# facewhisperer.net
KiCad netlist of a schematic drawn in EAGLE
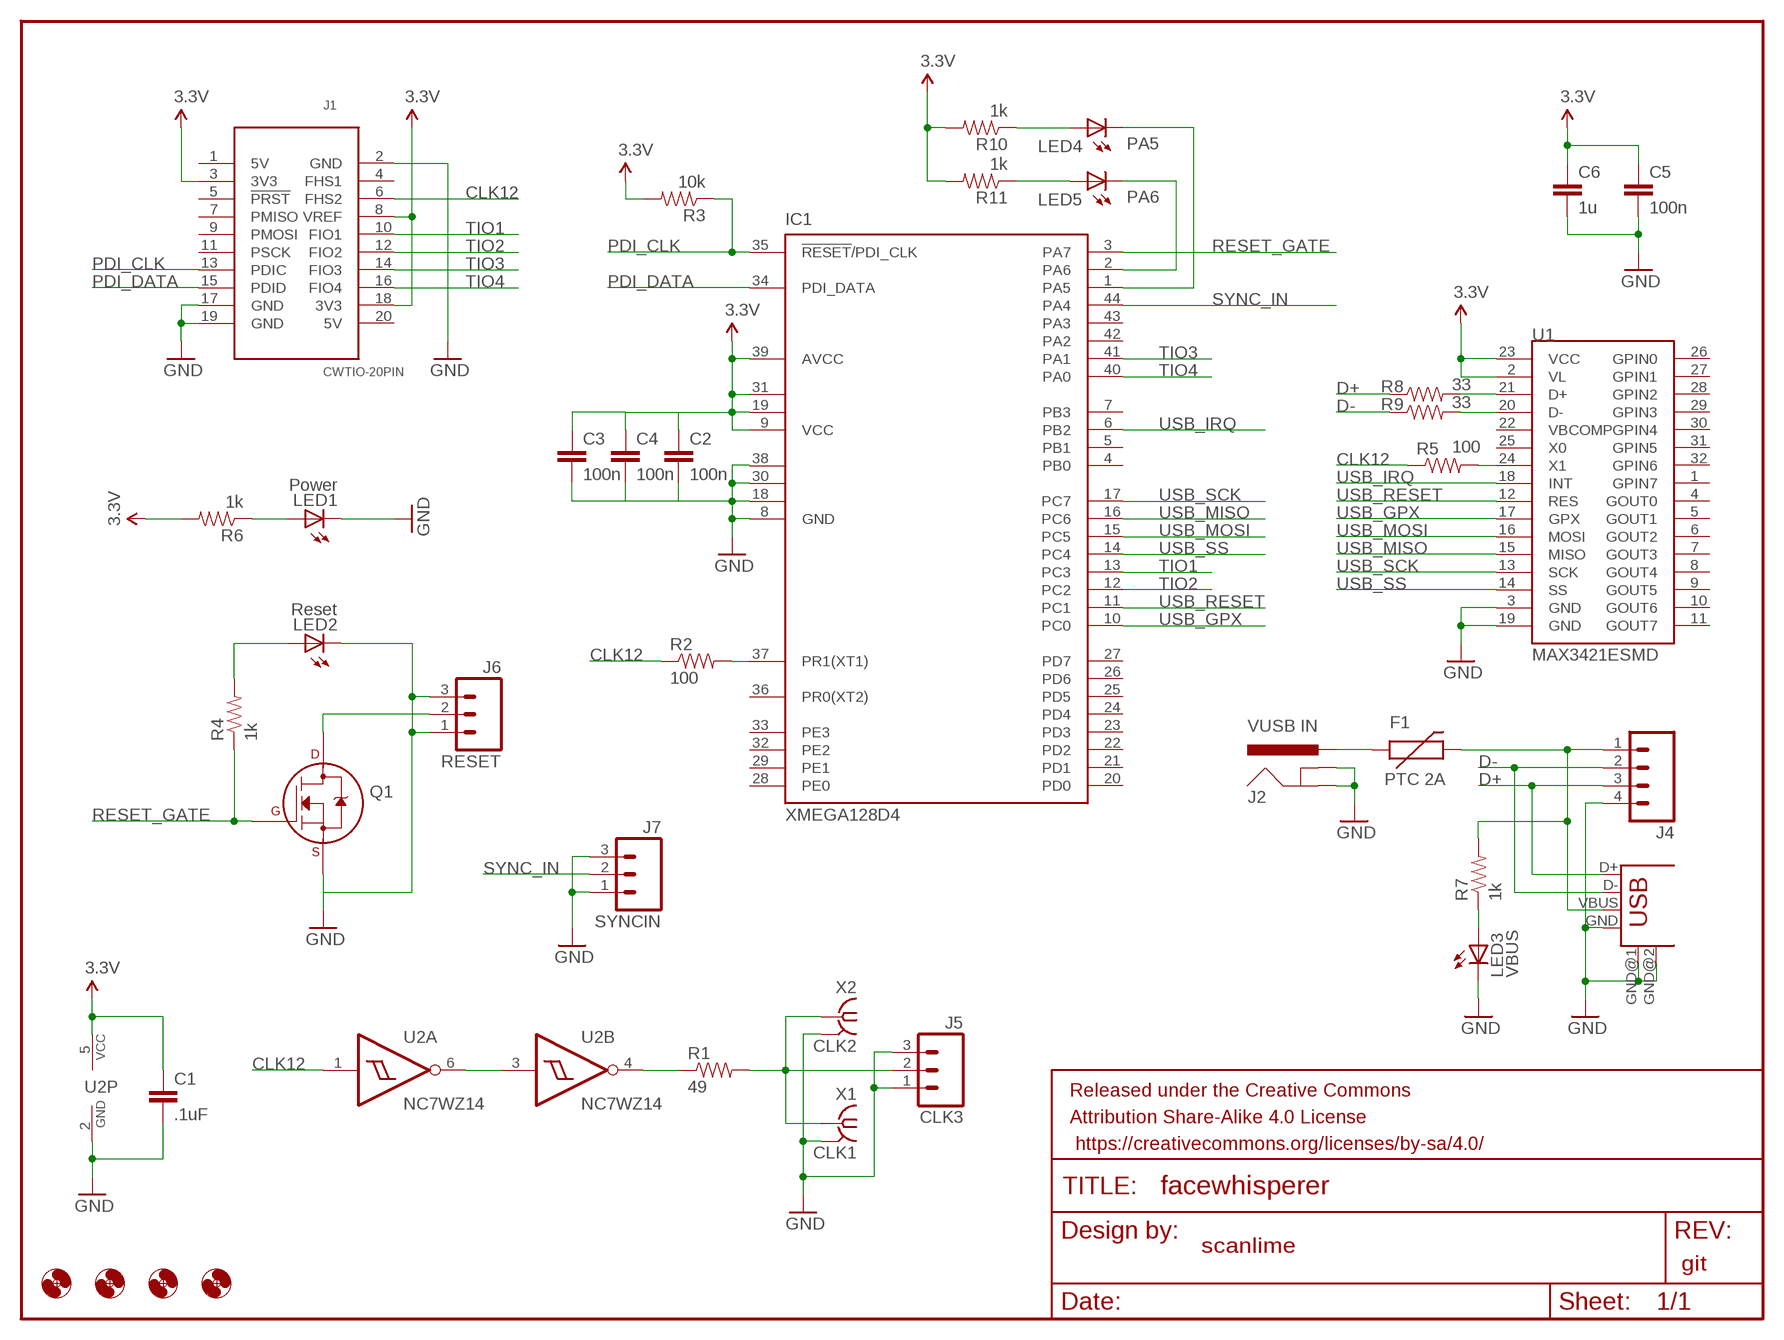
[diagram p0: schematic, sheet 1]

(export (version "E")
  (design (tool "Eeschema 10.0.6"))
  (components
    (comp (ref "C1")
      (value ".1uF")
      (footprint "eagle-import:0805")
      (libsource (lib "eagle-import") (part "CAP0805"))
    )
    (comp (ref "C2")
      (value "100n")
      (footprint "eagle-import:0805")
      (libsource (lib "eagle-import") (part "CAP0805"))
    )
    (comp (ref "C3")
      (value "100n")
      (footprint "eagle-import:0805")
      (libsource (lib "eagle-import") (part "CAP0805"))
    )
    (comp (ref "C4")
      (value "100n")
      (footprint "eagle-import:0805")
      (libsource (lib "eagle-import") (part "CAP0805"))
    )
    (comp (ref "C5")
      (value "100n")
      (footprint "eagle-import:0805")
      (libsource (lib "eagle-import") (part "CAP0805"))
    )
    (comp (ref "C6")
      (value "1u")
      (footprint "eagle-import:0805")
      (libsource (lib "eagle-import") (part "CAP0805"))
    )
    (comp (ref "F1")
      (value "PTC 2A")
      (footprint "eagle-import:PTC-1206-WIDE")
      (libsource (lib "eagle-import") (part "PTCSMD-W"))
    )
    (comp (ref "FRAME1")
      (value "FRAME-LETTERNO_PACKAGE")
      (footprint "eagle-import:DUMMY")
      (fields (field (name "DESIGNER") "Nobody"))
      (libsource (lib "eagle-import") (part "FRAME-LETTERNO_PACKAGE"))
    )
    (comp (ref "H1")
      (value "MOUNT-HOLE3.2")
      (footprint "eagle-import:3,2")
      (libsource (lib "eagle-import") (part "MOUNT-HOLE3.2"))
    )
    (comp (ref "H2")
      (value "MOUNT-HOLE3.2")
      (footprint "eagle-import:3,2")
      (libsource (lib "eagle-import") (part "MOUNT-HOLE3.2"))
    )
    (comp (ref "H3")
      (value "MOUNT-HOLE3.2")
      (footprint "eagle-import:3,2")
      (libsource (lib "eagle-import") (part "MOUNT-HOLE3.2"))
    )
    (comp (ref "H4")
      (value "MOUNT-HOLE3.2")
      (footprint "eagle-import:3,2")
      (libsource (lib "eagle-import") (part "MOUNT-HOLE3.2"))
    )
    (comp (ref "IC1")
      (value "XMEGA128D4")
      (footprint "eagle-import:TQFP44")
      (libsource (lib "eagle-import") (part "XMEGA16A4A"))
    )
    (comp (ref "J1")
      (value "CWTIO-20PIN")
      (footprint "eagle-import:PINSHRD_PTH_2X10")
      (libsource (lib "eagle-import") (part "CWTIO-20PIN"))
    )
    (comp (ref "J2")
      (value "VUSB IN")
      (footprint "eagle-import:POWER_JACK_PTH")
      (libsource (lib "eagle-import") (part "POWER_JACKPTH"))
    )
    (comp (ref "J3")
      (value "USB-A-H")
      (footprint "eagle-import:USB-A-H")
      (libsource (lib "eagle-import") (part "USB-A-H"))
    )
    (comp (ref "J4")
      (value "M04LOCK_LONGPADS")
      (footprint "eagle-import:1X04_LOCK_LONGPADS")
      (libsource (lib "eagle-import") (part "M04LOCK_LONGPADS"))
    )
    (comp (ref "J5")
      (value "CLK3")
      (footprint "eagle-import:1X03_LOCK_LONGPADS")
      (libsource (lib "eagle-import") (part "M03LOCK_LONGPADS"))
    )
    (comp (ref "J6")
      (value "RESET")
      (footprint "eagle-import:1X03_LOCK_LONGPADS")
      (libsource (lib "eagle-import") (part "M03LOCK_LONGPADS"))
    )
    (comp (ref "J7")
      (value "SYNCIN")
      (footprint "eagle-import:1X03_LOCK_LONGPADS")
      (libsource (lib "eagle-import") (part "M03LOCK_LONGPADS"))
    )
    (comp (ref "LED1")
      (value "Power")
      (footprint "eagle-import:1206")
      (libsource (lib "eagle-import") (part "LEDSMT1206"))
    )
    (comp (ref "LED2")
      (value "Reset")
      (footprint "eagle-import:1206")
      (libsource (lib "eagle-import") (part "LEDSMT1206"))
    )
    (comp (ref "LED3")
      (value "VBUS")
      (footprint "eagle-import:1206")
      (libsource (lib "eagle-import") (part "LEDSMT1206"))
    )
    (comp (ref "LED4")
      (value "PA5")
      (footprint "eagle-import:1206")
      (libsource (lib "eagle-import") (part "LEDSMT1206"))
    )
    (comp (ref "LED5")
      (value "PA6")
      (footprint "eagle-import:1206")
      (libsource (lib "eagle-import") (part "LEDSMT1206"))
    )
    (comp (ref "Q1")
      (value "2N7002_SOT23")
      (footprint "eagle-import:SOT-23")
      (libsource (lib "eagle-import") (part "2N700_SOT232"))
    )
    (comp (ref "R1")
      (value "49")
      (footprint "eagle-import:0805")
      (libsource (lib "eagle-import") (part "RESISTOR0805-RES"))
    )
    (comp (ref "R2")
      (value "100")
      (footprint "eagle-import:0805")
      (libsource (lib "eagle-import") (part "RESISTOR0805-RES"))
    )
    (comp (ref "R3")
      (value "10k")
      (footprint "eagle-import:0805")
      (libsource (lib "eagle-import") (part "RESISTOR0805-RES"))
    )
    (comp (ref "R4")
      (value "1k")
      (footprint "eagle-import:0805")
      (libsource (lib "eagle-import") (part "RESISTOR0805-RES"))
    )
    (comp (ref "R5")
      (value "100")
      (footprint "eagle-import:0805")
      (libsource (lib "eagle-import") (part "RESISTOR0805-RES"))
    )
    (comp (ref "R6")
      (value "1k")
      (footprint "eagle-import:0805")
      (libsource (lib "eagle-import") (part "RESISTOR0805-RES"))
    )
    (comp (ref "R7")
      (value "1k")
      (footprint "eagle-import:0805")
      (libsource (lib "eagle-import") (part "RESISTOR0805-RES"))
    )
    (comp (ref "R8")
      (value "33")
      (footprint "eagle-import:0805")
      (libsource (lib "eagle-import") (part "RESISTOR0805-RES"))
    )
    (comp (ref "R9")
      (value "33")
      (footprint "eagle-import:0805")
      (libsource (lib "eagle-import") (part "RESISTOR0805-RES"))
    )
    (comp (ref "R10")
      (value "1k")
      (footprint "eagle-import:0805")
      (libsource (lib "eagle-import") (part "RESISTOR0805-RES"))
    )
    (comp (ref "R11")
      (value "1k")
      (footprint "eagle-import:0805")
      (libsource (lib "eagle-import") (part "RESISTOR0805-RES"))
    )
    (comp (ref "U1")
      (value "MAX3421ESMD")
      (footprint "eagle-import:TQFP32-5MM-MILLABLE")
      (libsource (lib "eagle-import") (part "MAX3421ESMD"))
    )
    (comp (ref "U2")
      (value "NC7WZ14")
      (footprint "eagle-import:SC70-6-MILLABLE")
      (libsource (lib "eagle-import") (part "NC7WZ14"))
    )
    (comp (ref "X1")
      (value "CLK1")
      (footprint "eagle-import:J502-ND-142-0711-821_826-NOSILK")
      (libsource (lib "eagle-import") (part "SMA-NOSILK"))
    )
    (comp (ref "X2")
      (value "CLK2")
      (footprint "eagle-import:J502-ND-142-0711-821_826-NOSILK")
      (libsource (lib "eagle-import") (part "SMA-NOSILK"))
    )
  )
  (nets
    (net (code "1") (name "/CLK12") (class "Default")
      (node (ref "J1") (pin "6") (pinfunction "FHS2_6") (pintype "bidirectional"))
      (node (ref "R2") (pin "1") (pinfunction "1_1") (pintype "passive"))
      (node (ref "R5") (pin "1") (pinfunction "1_1") (pintype "passive"))
      (node (ref "U2") (pin "1") (pinfunction "IN_1") (pintype "input"))
    )
    (net (code "2") (name "/D+") (class "Default")
      (node (ref "J3") (pin "D+") (pinfunction "D+_D+") (pintype "bidirectional"))
      (node (ref "J4") (pin "3") (pinfunction "3_3") (pintype "passive"))
      (node (ref "R8") (pin "1") (pinfunction "1_1") (pintype "passive"))
    )
    (net (code "3") (name "/D-") (class "Default")
      (node (ref "J3") (pin "D-") (pinfunction "D-_D-") (pintype "bidirectional"))
      (node (ref "J4") (pin "2") (pinfunction "2_2") (pintype "passive"))
      (node (ref "R9") (pin "1") (pinfunction "1_1") (pintype "passive"))
    )
    (net (code "4") (name "/PDI_CLK") (class "Default")
      (node (ref "IC1") (pin "35") (pinfunction "~{RESET}/PDI_CLK_35") (pintype "bidirectional"))
      (node (ref "J1") (pin "13") (pinfunction "PDIC_13") (pintype "bidirectional"))
      (node (ref "R3") (pin "1") (pinfunction "1_1") (pintype "passive"))
    )
    (net (code "5") (name "/PDI_DATA") (class "Default")
      (node (ref "IC1") (pin "34") (pinfunction "PDI_DATA_34") (pintype "bidirectional"))
      (node (ref "J1") (pin "15") (pinfunction "PDID_15") (pintype "bidirectional"))
    )
    (net (code "6") (name "/RESET_GATE") (class "Default")
      (node (ref "IC1") (pin "3") (pinfunction "PA7_3") (pintype "bidirectional"))
      (node (ref "Q1") (pin "1") (pinfunction "G_1") (pintype "tri_state"))
      (node (ref "R4") (pin "1") (pinfunction "1_1") (pintype "passive"))
    )
    (net (code "7") (name "/SYNC_IN") (class "Default")
      (node (ref "IC1") (pin "44") (pinfunction "PA4_44") (pintype "bidirectional"))
      (node (ref "J7") (pin "2") (pinfunction "2_2") (pintype "passive"))
    )
    (net (code "8") (name "/TIO1") (class "Default")
      (node (ref "IC1") (pin "13") (pinfunction "PC3_13") (pintype "bidirectional"))
      (node (ref "J1") (pin "10") (pinfunction "FIO1_10") (pintype "bidirectional"))
    )
    (net (code "9") (name "/TIO2") (class "Default")
      (node (ref "IC1") (pin "12") (pinfunction "PC2_12") (pintype "bidirectional"))
      (node (ref "J1") (pin "12") (pinfunction "FIO2_12") (pintype "bidirectional"))
    )
    (net (code "10") (name "/TIO3") (class "Default")
      (node (ref "IC1") (pin "41") (pinfunction "PA1_41") (pintype "bidirectional"))
      (node (ref "J1") (pin "14") (pinfunction "FIO3_14") (pintype "bidirectional"))
    )
    (net (code "11") (name "/TIO4") (class "Default")
      (node (ref "IC1") (pin "40") (pinfunction "PA0_40") (pintype "bidirectional"))
      (node (ref "J1") (pin "16") (pinfunction "FIO4_16") (pintype "bidirectional"))
    )
    (net (code "12") (name "/USB_GPX") (class "Default")
      (node (ref "IC1") (pin "10") (pinfunction "PC0_10") (pintype "bidirectional"))
      (node (ref "U1") (pin "17") (pinfunction "GPX_17") (pintype "bidirectional"))
    )
    (net (code "13") (name "/USB_IRQ") (class "Default")
      (node (ref "IC1") (pin "6") (pinfunction "PB2_6") (pintype "bidirectional"))
      (node (ref "U1") (pin "18") (pinfunction "INT_18") (pintype "bidirectional"))
    )
    (net (code "14") (name "/USB_MISO") (class "Default")
      (node (ref "IC1") (pin "16") (pinfunction "PC6_16") (pintype "bidirectional"))
      (node (ref "U1") (pin "15") (pinfunction "MISO_15") (pintype "bidirectional"))
    )
    (net (code "15") (name "/USB_MOSI") (class "Default")
      (node (ref "IC1") (pin "15") (pinfunction "PC5_15") (pintype "bidirectional"))
      (node (ref "U1") (pin "16") (pinfunction "MOSI_16") (pintype "bidirectional"))
    )
    (net (code "16") (name "/USB_RESET") (class "Default")
      (node (ref "IC1") (pin "11") (pinfunction "PC1_11") (pintype "bidirectional"))
      (node (ref "U1") (pin "12") (pinfunction "RES_12") (pintype "bidirectional"))
    )
    (net (code "17") (name "/USB_SCK") (class "Default")
      (node (ref "IC1") (pin "17") (pinfunction "PC7_17") (pintype "bidirectional"))
      (node (ref "U1") (pin "13") (pinfunction "SCK_13") (pintype "bidirectional"))
    )
    (net (code "18") (name "/USB_SS") (class "Default")
      (node (ref "IC1") (pin "14") (pinfunction "PC4_14") (pintype "bidirectional"))
      (node (ref "U1") (pin "14") (pinfunction "SS_14") (pintype "bidirectional"))
    )
    (net (code "19") (name "3.3V") (class "Default")
      (node (ref "C1") (pin "1") (pinfunction "1_1") (pintype "passive"))
      (node (ref "C2") (pin "1") (pinfunction "1_1") (pintype "passive"))
      (node (ref "C3") (pin "1") (pinfunction "1_1") (pintype "passive"))
      (node (ref "C4") (pin "1") (pinfunction "1_1") (pintype "passive"))
      (node (ref "C5") (pin "1") (pinfunction "1_1") (pintype "passive"))
      (node (ref "C6") (pin "1") (pinfunction "1_1") (pintype "passive"))
      (node (ref "IC1") (pin "19") (pinfunction "VCC1_19") (pintype "power_in"))
      (node (ref "IC1") (pin "31") (pinfunction "VCC2_31") (pintype "power_in"))
      (node (ref "IC1") (pin "39") (pinfunction "AVCC_39") (pintype "power_in"))
      (node (ref "IC1") (pin "9") (pinfunction "VCC_9") (pintype "power_in"))
      (node (ref "J1") (pin "18") (pinfunction "3V3_18") (pintype "bidirectional"))
      (node (ref "J1") (pin "3") (pinfunction "3V3_3") (pintype "bidirectional"))
      (node (ref "J1") (pin "8") (pinfunction "VREF_8") (pintype "bidirectional"))
      (node (ref "R10") (pin "2") (pinfunction "2_2") (pintype "passive"))
      (node (ref "R11") (pin "2") (pinfunction "2_2") (pintype "passive"))
      (node (ref "R3") (pin "2") (pinfunction "2_2") (pintype "passive"))
      (node (ref "R6") (pin "2") (pinfunction "2_2") (pintype "passive"))
      (node (ref "U1") (pin "2") (pinfunction "VL_2") (pintype "bidirectional"))
      (node (ref "U1") (pin "23") (pinfunction "VCC_23") (pintype "bidirectional"))
      (node (ref "U2") (pin "5") (pinfunction "VCC_5") (pintype "power_in"))
    )
    (net (code "20") (name "GND") (class "Default")
      (node (ref "C1") (pin "2") (pinfunction "2_2") (pintype "passive"))
      (node (ref "C2") (pin "2") (pinfunction "2_2") (pintype "passive"))
      (node (ref "C3") (pin "2") (pinfunction "2_2") (pintype "passive"))
      (node (ref "C4") (pin "2") (pinfunction "2_2") (pintype "passive"))
      (node (ref "C5") (pin "2") (pinfunction "2_2") (pintype "passive"))
      (node (ref "C6") (pin "2") (pinfunction "2_2") (pintype "passive"))
      (node (ref "IC1") (pin "18") (pinfunction "GND1_18") (pintype "power_in"))
      (node (ref "IC1") (pin "30") (pinfunction "GND2_30") (pintype "power_in"))
      (node (ref "IC1") (pin "38") (pinfunction "GND3_38") (pintype "power_in"))
      (node (ref "IC1") (pin "8") (pinfunction "GND_8") (pintype "power_in"))
      (node (ref "J1") (pin "17") (pinfunction "GND_17") (pintype "bidirectional"))
      (node (ref "J1") (pin "19") (pinfunction "GND_19") (pintype "bidirectional"))
      (node (ref "J1") (pin "2") (pinfunction "GND_2") (pintype "bidirectional"))
      (node (ref "J2") (pin "GND") (pinfunction "GND_GND") (pintype "bidirectional"))
      (node (ref "J2") (pin "GNDBREAK") (pinfunction "GNDBREAK_GNDBREAK") (pintype "bidirectional"))
      (node (ref "J3") (pin "GND") (pinfunction "GND_GND") (pintype "bidirectional"))
      (node (ref "J3") (pin "GND@1") (pinfunction "GND_GND@1") (pintype "bidirectional"))
      (node (ref "J3") (pin "GND@2") (pinfunction "GND_GND@2") (pintype "bidirectional"))
      (node (ref "J4") (pin "4") (pinfunction "4_4") (pintype "passive"))
      (node (ref "J5") (pin "1") (pinfunction "1_1") (pintype "passive"))
      (node (ref "J5") (pin "3") (pinfunction "3_3") (pintype "passive"))
      (node (ref "J6") (pin "1") (pinfunction "1_1") (pintype "passive"))
      (node (ref "J6") (pin "3") (pinfunction "3_3") (pintype "passive"))
      (node (ref "J7") (pin "1") (pinfunction "1_1") (pintype "passive"))
      (node (ref "J7") (pin "3") (pinfunction "3_3") (pintype "passive"))
      (node (ref "LED1") (pin "C") (pinfunction "C_C") (pintype "passive"))
      (node (ref "LED2") (pin "C") (pinfunction "C_C") (pintype "passive"))
      (node (ref "LED3") (pin "C") (pinfunction "C_C") (pintype "passive"))
      (node (ref "Q1") (pin "2") (pinfunction "S_2") (pintype "bidirectional"))
      (node (ref "U1") (pin "19") (pinfunction "GND_19") (pintype "bidirectional"))
      (node (ref "U1") (pin "3") (pinfunction "GND_3") (pintype "bidirectional"))
      (node (ref "U2") (pin "2") (pinfunction "GND_2") (pintype "power_in"))
      (node (ref "X1") (pin "G@1") (pinfunction "2_G@1") (pintype "passive"))
      (node (ref "X1") (pin "G@2") (pinfunction "2_G@2") (pintype "passive"))
      (node (ref "X1") (pin "G@3") (pinfunction "2_G@3") (pintype "passive"))
      (node (ref "X1") (pin "G@4") (pinfunction "2_G@4") (pintype "passive"))
      (node (ref "X2") (pin "G@1") (pinfunction "2_G@1") (pintype "passive"))
      (node (ref "X2") (pin "G@2") (pinfunction "2_G@2") (pintype "passive"))
      (node (ref "X2") (pin "G@3") (pinfunction "2_G@3") (pintype "passive"))
      (node (ref "X2") (pin "G@4") (pinfunction "2_G@4") (pintype "passive"))
    )
    (net (code "21") (name "Net-(F1-Pad1)") (class "Default")
      (node (ref "F1") (pin "1") (pinfunction "1_1") (pintype "bidirectional"))
      (node (ref "J2") (pin "PWR") (pinfunction "PWR_PWR") (pintype "bidirectional"))
    )
    (net (code "22") (name "Net-(F1-Pad2)") (class "Default")
      (node (ref "F1") (pin "2") (pinfunction "2_2") (pintype "bidirectional"))
      (node (ref "J3") (pin "VBUS") (pinfunction "VBUS_VBUS") (pintype "bidirectional"))
      (node (ref "J4") (pin "1") (pinfunction "1_1") (pintype "passive"))
      (node (ref "R7") (pin "2") (pinfunction "2_2") (pintype "passive"))
    )
    (net (code "23") (name "Net-(IC1-PA5)") (class "Default")
      (node (ref "IC1") (pin "1") (pinfunction "PA5_1") (pintype "bidirectional"))
      (node (ref "LED4") (pin "C") (pinfunction "C_C") (pintype "passive"))
    )
    (net (code "24") (name "Net-(IC1-PA6)") (class "Default")
      (node (ref "IC1") (pin "2") (pinfunction "PA6_2") (pintype "bidirectional"))
      (node (ref "LED5") (pin "C") (pinfunction "C_C") (pintype "passive"))
    )
    (net (code "25") (name "Net-(IC1-PR1(XT1))") (class "Default")
      (node (ref "IC1") (pin "37") (pinfunction "PR1(XT1)_37") (pintype "bidirectional"))
      (node (ref "R2") (pin "2") (pinfunction "2_2") (pintype "passive"))
    )
    (net (code "26") (name "Net-(J5-Pad2)") (class "Default")
      (node (ref "J5") (pin "2") (pinfunction "2_2") (pintype "passive"))
      (node (ref "R1") (pin "2") (pinfunction "2_2") (pintype "passive"))
      (node (ref "X1") (pin "1") (pinfunction "1_1") (pintype "passive"))
      (node (ref "X2") (pin "1") (pinfunction "1_1") (pintype "passive"))
    )
    (net (code "27") (name "Net-(LED1-PadA)") (class "Default")
      (node (ref "LED1") (pin "A") (pinfunction "A_A") (pintype "passive"))
      (node (ref "R6") (pin "1") (pinfunction "1_1") (pintype "passive"))
    )
    (net (code "28") (name "Net-(LED2-PadA)") (class "Default")
      (node (ref "LED2") (pin "A") (pinfunction "A_A") (pintype "passive"))
      (node (ref "R4") (pin "2") (pinfunction "2_2") (pintype "passive"))
    )
    (net (code "29") (name "Net-(LED3-PadA)") (class "Default")
      (node (ref "LED3") (pin "A") (pinfunction "A_A") (pintype "passive"))
      (node (ref "R7") (pin "1") (pinfunction "1_1") (pintype "passive"))
    )
    (net (code "30") (name "Net-(LED4-PadA)") (class "Default")
      (node (ref "LED4") (pin "A") (pinfunction "A_A") (pintype "passive"))
      (node (ref "R10") (pin "1") (pinfunction "1_1") (pintype "passive"))
    )
    (net (code "31") (name "Net-(LED5-PadA)") (class "Default")
      (node (ref "LED5") (pin "A") (pinfunction "A_A") (pintype "passive"))
      (node (ref "R11") (pin "1") (pinfunction "1_1") (pintype "passive"))
    )
    (net (code "32") (name "Net-(Q1-D)") (class "Default")
      (node (ref "J6") (pin "2") (pinfunction "2_2") (pintype "passive"))
      (node (ref "Q1") (pin "3") (pinfunction "D_3") (pintype "bidirectional"))
    )
    (net (code "33") (name "Net-(U1-D+)") (class "Default")
      (node (ref "R8") (pin "2") (pinfunction "2_2") (pintype "passive"))
      (node (ref "U1") (pin "21") (pinfunction "D+_21") (pintype "bidirectional"))
    )
    (net (code "34") (name "Net-(U1-D-)") (class "Default")
      (node (ref "R9") (pin "2") (pinfunction "2_2") (pintype "passive"))
      (node (ref "U1") (pin "20") (pinfunction "D-_20") (pintype "bidirectional"))
    )
    (net (code "35") (name "Net-(U1-X1)") (class "Default")
      (node (ref "R5") (pin "2") (pinfunction "2_2") (pintype "passive"))
      (node (ref "U1") (pin "24") (pinfunction "X1_24") (pintype "bidirectional"))
    )
    (net (code "36") (name "Net-(U2A-OUT)") (class "Default")
      (node (ref "U2") (pin "3") (pinfunction "IN_3") (pintype "input"))
      (node (ref "U2") (pin "6") (pinfunction "OUT_6") (pintype "output"))
    )
    (net (code "37") (name "Net-(U2B-OUT)") (class "Default")
      (node (ref "R1") (pin "1") (pinfunction "1_1") (pintype "passive"))
      (node (ref "U2") (pin "4") (pinfunction "OUT_4") (pintype "output"))
    )
    (net (code "38") (name "unconnected-(IC1-PA2-Pad42)") (class "Default")
      (node (ref "IC1") (pin "42") (pinfunction "PA2_42") (pintype "bidirectional"))
    )
    (net (code "39") (name "unconnected-(IC1-PA3-Pad43)") (class "Default")
      (node (ref "IC1") (pin "43") (pinfunction "PA3_43") (pintype "bidirectional"))
    )
    (net (code "40") (name "unconnected-(IC1-PB0-Pad4)") (class "Default")
      (node (ref "IC1") (pin "4") (pinfunction "PB0_4") (pintype "bidirectional"))
    )
    (net (code "41") (name "unconnected-(IC1-PB1-Pad5)") (class "Default")
      (node (ref "IC1") (pin "5") (pinfunction "PB1_5") (pintype "bidirectional"))
    )
    (net (code "42") (name "unconnected-(IC1-PB3-Pad7)") (class "Default")
      (node (ref "IC1") (pin "7") (pinfunction "PB3_7") (pintype "bidirectional"))
    )
    (net (code "43") (name "unconnected-(IC1-PD0-Pad20)") (class "Default")
      (node (ref "IC1") (pin "20") (pinfunction "PD0_20") (pintype "bidirectional"))
    )
    (net (code "44") (name "unconnected-(IC1-PD1-Pad21)") (class "Default")
      (node (ref "IC1") (pin "21") (pinfunction "PD1_21") (pintype "bidirectional"))
    )
    (net (code "45") (name "unconnected-(IC1-PD2-Pad22)") (class "Default")
      (node (ref "IC1") (pin "22") (pinfunction "PD2_22") (pintype "bidirectional"))
    )
    (net (code "46") (name "unconnected-(IC1-PD3-Pad23)") (class "Default")
      (node (ref "IC1") (pin "23") (pinfunction "PD3_23") (pintype "bidirectional"))
    )
    (net (code "47") (name "unconnected-(IC1-PD4-Pad24)") (class "Default")
      (node (ref "IC1") (pin "24") (pinfunction "PD4_24") (pintype "bidirectional"))
    )
    (net (code "48") (name "unconnected-(IC1-PD5-Pad25)") (class "Default")
      (node (ref "IC1") (pin "25") (pinfunction "PD5_25") (pintype "bidirectional"))
    )
    (net (code "49") (name "unconnected-(IC1-PD6-Pad26)") (class "Default")
      (node (ref "IC1") (pin "26") (pinfunction "PD6_26") (pintype "bidirectional"))
    )
    (net (code "50") (name "unconnected-(IC1-PD7-Pad27)") (class "Default")
      (node (ref "IC1") (pin "27") (pinfunction "PD7_27") (pintype "bidirectional"))
    )
    (net (code "51") (name "unconnected-(IC1-PE0-Pad28)") (class "Default")
      (node (ref "IC1") (pin "28") (pinfunction "PE0_28") (pintype "bidirectional"))
    )
    (net (code "52") (name "unconnected-(IC1-PE1-Pad29)") (class "Default")
      (node (ref "IC1") (pin "29") (pinfunction "PE1_29") (pintype "bidirectional"))
    )
    (net (code "53") (name "unconnected-(IC1-PE2-Pad32)") (class "Default")
      (node (ref "IC1") (pin "32") (pinfunction "PE2_32") (pintype "bidirectional"))
    )
    (net (code "54") (name "unconnected-(IC1-PE3-Pad33)") (class "Default")
      (node (ref "IC1") (pin "33") (pinfunction "PE3_33") (pintype "bidirectional"))
    )
    (net (code "55") (name "unconnected-(IC1-PR0(XT2)-Pad36)") (class "Default")
      (node (ref "IC1") (pin "36") (pinfunction "PR0(XT2)_36") (pintype "bidirectional"))
    )
    (net (code "56") (name "unconnected-(J1-5V-Pad1)") (class "Default")
      (node (ref "J1") (pin "1") (pinfunction "5V_1") (pintype "bidirectional"))
    )
    (net (code "57") (name "unconnected-(J1-5V-Pad20)") (class "Default")
      (node (ref "J1") (pin "20") (pinfunction "5V_20") (pintype "bidirectional"))
    )
    (net (code "58") (name "unconnected-(J1-FHS1-Pad4)") (class "Default")
      (node (ref "J1") (pin "4") (pinfunction "FHS1_4") (pintype "bidirectional"))
    )
    (net (code "59") (name "unconnected-(J1-PMISO-Pad7)") (class "Default")
      (node (ref "J1") (pin "7") (pinfunction "PMISO_7") (pintype "bidirectional"))
    )
    (net (code "60") (name "unconnected-(J1-PMOSI-Pad9)") (class "Default")
      (node (ref "J1") (pin "9") (pinfunction "PMOSI_9") (pintype "bidirectional"))
    )
    (net (code "61") (name "unconnected-(J1-PSCK-Pad11)") (class "Default")
      (node (ref "J1") (pin "11") (pinfunction "PSCK_11") (pintype "bidirectional"))
    )
    (net (code "62") (name "unconnected-(J1-~{PRST}-Pad5)") (class "Default")
      (node (ref "J1") (pin "5") (pinfunction "~{PRST}_5") (pintype "bidirectional"))
    )
    (net (code "63") (name "unconnected-(U1-GOUT0-Pad4)") (class "Default")
      (node (ref "U1") (pin "4") (pinfunction "GOUT0_4") (pintype "bidirectional"))
    )
    (net (code "64") (name "unconnected-(U1-GOUT1-Pad5)") (class "Default")
      (node (ref "U1") (pin "5") (pinfunction "GOUT1_5") (pintype "bidirectional"))
    )
    (net (code "65") (name "unconnected-(U1-GOUT2-Pad6)") (class "Default")
      (node (ref "U1") (pin "6") (pinfunction "GOUT2_6") (pintype "bidirectional"))
    )
    (net (code "66") (name "unconnected-(U1-GOUT3-Pad7)") (class "Default")
      (node (ref "U1") (pin "7") (pinfunction "GOUT3_7") (pintype "bidirectional"))
    )
    (net (code "67") (name "unconnected-(U1-GOUT4-Pad8)") (class "Default")
      (node (ref "U1") (pin "8") (pinfunction "GOUT4_8") (pintype "bidirectional"))
    )
    (net (code "68") (name "unconnected-(U1-GOUT5-Pad9)") (class "Default")
      (node (ref "U1") (pin "9") (pinfunction "GOUT5_9") (pintype "bidirectional"))
    )
    (net (code "69") (name "unconnected-(U1-GOUT6-Pad10)") (class "Default")
      (node (ref "U1") (pin "10") (pinfunction "GOUT6_10") (pintype "bidirectional"))
    )
    (net (code "70") (name "unconnected-(U1-GOUT7-Pad11)") (class "Default")
      (node (ref "U1") (pin "11") (pinfunction "GOUT7_11") (pintype "bidirectional"))
    )
    (net (code "71") (name "unconnected-(U1-GPIN0-Pad26)") (class "Default")
      (node (ref "U1") (pin "26") (pinfunction "GPIN0_26") (pintype "bidirectional"))
    )
    (net (code "72") (name "unconnected-(U1-GPIN1-Pad27)") (class "Default")
      (node (ref "U1") (pin "27") (pinfunction "GPIN1_27") (pintype "bidirectional"))
    )
    (net (code "73") (name "unconnected-(U1-GPIN2-Pad28)") (class "Default")
      (node (ref "U1") (pin "28") (pinfunction "GPIN2_28") (pintype "bidirectional"))
    )
    (net (code "74") (name "unconnected-(U1-GPIN3-Pad29)") (class "Default")
      (node (ref "U1") (pin "29") (pinfunction "GPIN3_29") (pintype "bidirectional"))
    )
    (net (code "75") (name "unconnected-(U1-GPIN4-Pad30)") (class "Default")
      (node (ref "U1") (pin "30") (pinfunction "GPIN4_30") (pintype "bidirectional"))
    )
    (net (code "76") (name "unconnected-(U1-GPIN5-Pad31)") (class "Default")
      (node (ref "U1") (pin "31") (pinfunction "GPIN5_31") (pintype "bidirectional"))
    )
    (net (code "77") (name "unconnected-(U1-GPIN6-Pad32)") (class "Default")
      (node (ref "U1") (pin "32") (pinfunction "GPIN6_32") (pintype "bidirectional"))
    )
    (net (code "78") (name "unconnected-(U1-GPIN7-Pad1)") (class "Default")
      (node (ref "U1") (pin "1") (pinfunction "GPIN7_1") (pintype "bidirectional"))
    )
    (net (code "79") (name "unconnected-(U1-VBCOMP-Pad22)") (class "Default")
      (node (ref "U1") (pin "22") (pinfunction "VBCOMP_22") (pintype "bidirectional"))
    )
    (net (code "80") (name "unconnected-(U1-X0-Pad25)") (class "Default")
      (node (ref "U1") (pin "25") (pinfunction "X0_25") (pintype "bidirectional"))
    )
  )
)
